# chandelier.net
KiCad netlist of a schematic drawn in EAGLE
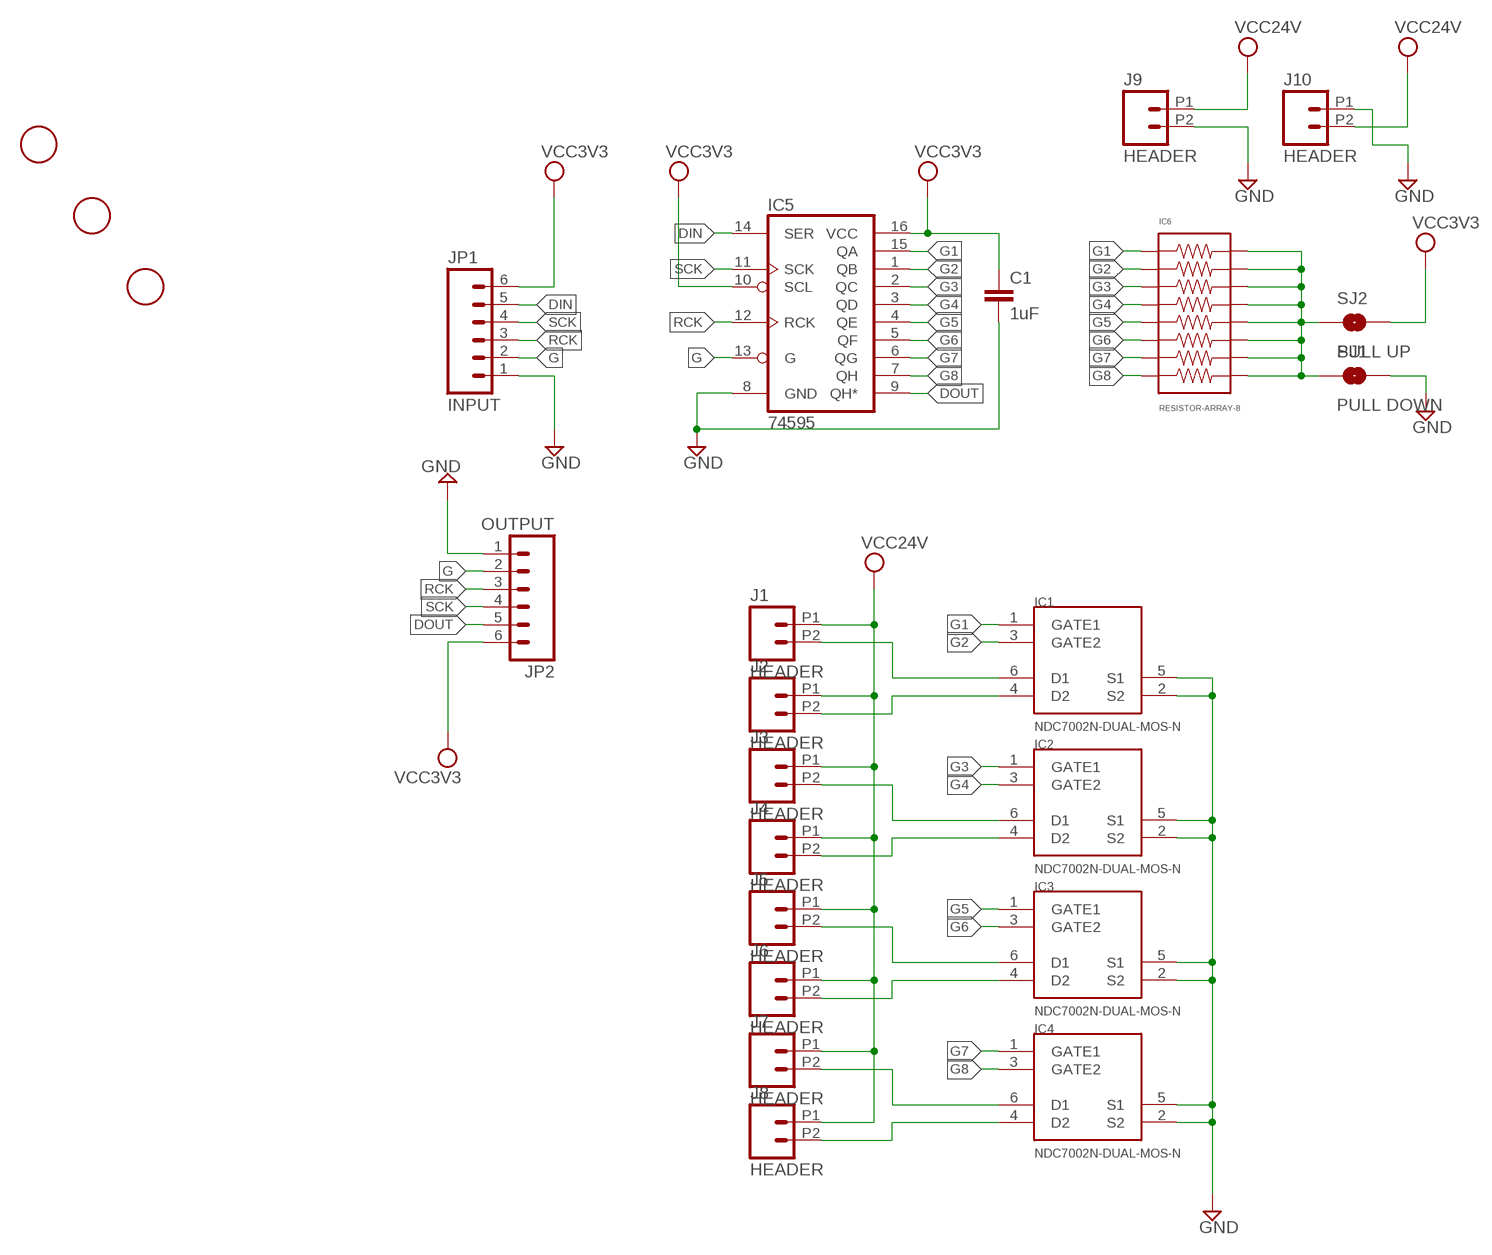
[diagram p0: schematic, sheet 1]

(export (version "E")
  (design (tool "Eeschema 10.0.6"))
  (components
    (comp (ref "C1")
      (value "1uF")
      (footprint "eagle-import:0805")
      (fields (field (name "PARTNO") "CL21B105KOFNNNE"))
      (libsource (lib "eagle-import") (part "CAP0805"))
    )
    (comp (ref "IC1")
      (value "NDC7002N-DUAL-MOS-N")
      (footprint "eagle-import:SSOT6")
      (fields (field (name "PARTNO") "NDC7002N"))
      (libsource (lib "eagle-import") (part "NDC7002N-DUAL-MOS-N"))
    )
    (comp (ref "IC2")
      (value "NDC7002N-DUAL-MOS-N")
      (footprint "eagle-import:SSOT6")
      (fields (field (name "PARTNO") "NDC7002N"))
      (libsource (lib "eagle-import") (part "NDC7002N-DUAL-MOS-N"))
    )
    (comp (ref "IC3")
      (value "NDC7002N-DUAL-MOS-N")
      (footprint "eagle-import:SSOT6")
      (fields (field (name "PARTNO") "NDC7002N"))
      (libsource (lib "eagle-import") (part "NDC7002N-DUAL-MOS-N"))
    )
    (comp (ref "IC4")
      (value "NDC7002N-DUAL-MOS-N")
      (footprint "eagle-import:SSOT6")
      (fields (field (name "PARTNO") "NDC7002N"))
      (libsource (lib "eagle-import") (part "NDC7002N-DUAL-MOS-N"))
    )
    (comp (ref "IC5")
      (value "74595")
      (footprint "eagle-import:TSSOP16")
      (fields (field (name "PARTNO") "74VHC595MTCX"))
      (libsource (lib "eagle-import") (part "74595"))
    )
    (comp (ref "IC6")
      (value "RESISTOR-ARRAY-8")
      (footprint "eagle-import:CAY16-103J8")
      (fields (field (name "PARTNO") "CAY16-103J8LF"))
      (libsource (lib "eagle-import") (part "RESISTOR-ARRAY-8"))
    )
    (comp (ref "J1")
      (value "HEADER")
      (footprint "eagle-import:1X02-5.08-SCREWTERM")
      (libsource (lib "eagle-import") (part "HEADER"))
    )
    (comp (ref "J2")
      (value "HEADER")
      (footprint "eagle-import:1X02-5.08-SCREWTERM")
      (libsource (lib "eagle-import") (part "HEADER"))
    )
    (comp (ref "J3")
      (value "HEADER")
      (footprint "eagle-import:1X02-5.08-SCREWTERM")
      (libsource (lib "eagle-import") (part "HEADER"))
    )
    (comp (ref "J4")
      (value "HEADER")
      (footprint "eagle-import:1X02-5.08-SCREWTERM")
      (libsource (lib "eagle-import") (part "HEADER"))
    )
    (comp (ref "J5")
      (value "HEADER")
      (footprint "eagle-import:1X02-5.08-SCREWTERM")
      (libsource (lib "eagle-import") (part "HEADER"))
    )
    (comp (ref "J6")
      (value "HEADER")
      (footprint "eagle-import:1X02-5.08-SCREWTERM")
      (libsource (lib "eagle-import") (part "HEADER"))
    )
    (comp (ref "J7")
      (value "HEADER")
      (footprint "eagle-import:1X02-5.08-SCREWTERM")
      (libsource (lib "eagle-import") (part "HEADER"))
    )
    (comp (ref "J8")
      (value "HEADER")
      (footprint "eagle-import:1X02-5.08-SCREWTERM")
      (libsource (lib "eagle-import") (part "HEADER"))
    )
    (comp (ref "J9")
      (value "HEADER")
      (footprint "eagle-import:1X02-5.08-SCREWTERM")
      (libsource (lib "eagle-import") (part "HEADER"))
    )
    (comp (ref "J10")
      (value "HEADER")
      (footprint "eagle-import:1X02-5.08-SCREWTERM")
      (libsource (lib "eagle-import") (part "HEADER"))
    )
    (comp (ref "JP1")
      (value "INPUT")
      (footprint "eagle-import:1X06-SIP_LOCK")
      (libsource (lib "eagle-import") (part "M06SIP_LOCK"))
    )
    (comp (ref "JP2")
      (value "OUTPUT")
      (footprint "eagle-import:1X06-SIP_LOCK")
      (libsource (lib "eagle-import") (part "M06SIP_LOCK"))
    )
    (comp (ref "SJ1")
      (value "PULL DOWN")
      (footprint "eagle-import:SJ_2S-TRACE")
      (libsource (lib "eagle-import") (part "SOLDERJUMPERTRACE"))
    )
    (comp (ref "SJ2")
      (value "PULL UP")
      (footprint "eagle-import:SJ_2S-NO")
      (libsource (lib "eagle-import") (part "SOLDERJUMPERNO"))
    )
    (comp (ref "U$1")
      (value "FIDUCIAL")
      (footprint "eagle-import:FIDUCIAL_1MM")
      (libsource (lib "eagle-import") (part "FIDUCIAL"))
    )
    (comp (ref "U$4")
      (value "FIDUCIAL")
      (footprint "eagle-import:FIDUCIAL_1MM")
      (libsource (lib "eagle-import") (part "FIDUCIAL"))
    )
    (comp (ref "U$5")
      (value "FIDUCIAL")
      (footprint "eagle-import:FIDUCIAL_1MM")
      (libsource (lib "eagle-import") (part "FIDUCIAL"))
    )
  )
  (nets
    (net (code "1") (name "DIN") (class "Default")
      (node (ref "IC5") (pin "14") (pinfunction "SER_14") (pintype "input"))
      (node (ref "JP1") (pin "5") (pinfunction "5_5") (pintype "passive"))
    )
    (net (code "2") (name "DOUT") (class "Default")
      (node (ref "IC5") (pin "9") (pinfunction "QH*_9") (pintype "tri_state"))
      (node (ref "JP2") (pin "5") (pinfunction "5_5") (pintype "passive"))
    )
    (net (code "3") (name "G") (class "Default")
      (node (ref "IC5") (pin "13") (pinfunction "G_13") (pintype "input"))
      (node (ref "JP1") (pin "2") (pinfunction "2_2") (pintype "passive"))
      (node (ref "JP2") (pin "2") (pinfunction "2_2") (pintype "passive"))
    )
    (net (code "4") (name "G1") (class "Default")
      (node (ref "IC1") (pin "1") (pinfunction "GATE1_1") (pintype "bidirectional"))
      (node (ref "IC5") (pin "15") (pinfunction "QA_15") (pintype "tri_state"))
      (node (ref "IC6") (pin "2") (pinfunction "2_2") (pintype "passive"))
    )
    (net (code "5") (name "G2") (class "Default")
      (node (ref "IC1") (pin "3") (pinfunction "GATE2_3") (pintype "bidirectional"))
      (node (ref "IC5") (pin "1") (pinfunction "QB_1") (pintype "tri_state"))
      (node (ref "IC6") (pin "4") (pinfunction "4_4") (pintype "passive"))
    )
    (net (code "6") (name "G3") (class "Default")
      (node (ref "IC2") (pin "1") (pinfunction "GATE1_1") (pintype "bidirectional"))
      (node (ref "IC5") (pin "2") (pinfunction "QC_2") (pintype "tri_state"))
      (node (ref "IC6") (pin "6") (pinfunction "6_6") (pintype "passive"))
    )
    (net (code "7") (name "G4") (class "Default")
      (node (ref "IC2") (pin "3") (pinfunction "GATE2_3") (pintype "bidirectional"))
      (node (ref "IC5") (pin "3") (pinfunction "QD_3") (pintype "tri_state"))
      (node (ref "IC6") (pin "8") (pinfunction "8_8") (pintype "passive"))
    )
    (net (code "8") (name "G5") (class "Default")
      (node (ref "IC3") (pin "1") (pinfunction "GATE1_1") (pintype "bidirectional"))
      (node (ref "IC5") (pin "4") (pinfunction "QE_4") (pintype "tri_state"))
      (node (ref "IC6") (pin "10") (pinfunction "10_10") (pintype "passive"))
    )
    (net (code "9") (name "G6") (class "Default")
      (node (ref "IC3") (pin "3") (pinfunction "GATE2_3") (pintype "bidirectional"))
      (node (ref "IC5") (pin "5") (pinfunction "QF_5") (pintype "tri_state"))
      (node (ref "IC6") (pin "12") (pinfunction "12_12") (pintype "passive"))
    )
    (net (code "10") (name "G7") (class "Default")
      (node (ref "IC4") (pin "1") (pinfunction "GATE1_1") (pintype "bidirectional"))
      (node (ref "IC5") (pin "6") (pinfunction "QG_6") (pintype "tri_state"))
      (node (ref "IC6") (pin "14") (pinfunction "14_14") (pintype "passive"))
    )
    (net (code "11") (name "G8") (class "Default")
      (node (ref "IC4") (pin "3") (pinfunction "GATE2_3") (pintype "bidirectional"))
      (node (ref "IC5") (pin "7") (pinfunction "QH_7") (pintype "tri_state"))
      (node (ref "IC6") (pin "16") (pinfunction "16_16") (pintype "passive"))
    )
    (net (code "12") (name "GND") (class "Default")
      (node (ref "C1") (pin "2") (pinfunction "2_2") (pintype "passive"))
      (node (ref "IC1") (pin "2") (pinfunction "S2_2") (pintype "bidirectional"))
      (node (ref "IC1") (pin "5") (pinfunction "S1_5") (pintype "bidirectional"))
      (node (ref "IC2") (pin "2") (pinfunction "S2_2") (pintype "bidirectional"))
      (node (ref "IC2") (pin "5") (pinfunction "S1_5") (pintype "bidirectional"))
      (node (ref "IC3") (pin "2") (pinfunction "S2_2") (pintype "bidirectional"))
      (node (ref "IC3") (pin "5") (pinfunction "S1_5") (pintype "bidirectional"))
      (node (ref "IC4") (pin "2") (pinfunction "S2_2") (pintype "bidirectional"))
      (node (ref "IC4") (pin "5") (pinfunction "S1_5") (pintype "bidirectional"))
      (node (ref "IC5") (pin "8") (pinfunction "GND_8") (pintype "power_in"))
      (node (ref "J10") (pin "P1") (pinfunction "2_P1") (pintype "passive"))
      (node (ref "J9") (pin "P2") (pinfunction "1_P2") (pintype "passive"))
      (node (ref "JP1") (pin "1") (pinfunction "1_1") (pintype "passive"))
      (node (ref "JP2") (pin "1") (pinfunction "1_1") (pintype "passive"))
      (node (ref "SJ1") (pin "2") (pinfunction "2_2") (pintype "passive"))
    )
    (net (code "13") (name "Net-(IC1-D1)") (class "Default")
      (node (ref "IC1") (pin "6") (pinfunction "D1_6") (pintype "bidirectional"))
      (node (ref "J1") (pin "P2") (pinfunction "1_P2") (pintype "passive"))
    )
    (net (code "14") (name "Net-(IC1-D2)") (class "Default")
      (node (ref "IC1") (pin "4") (pinfunction "D2_4") (pintype "bidirectional"))
      (node (ref "J2") (pin "P2") (pinfunction "1_P2") (pintype "passive"))
    )
    (net (code "15") (name "Net-(IC2-D1)") (class "Default")
      (node (ref "IC2") (pin "6") (pinfunction "D1_6") (pintype "bidirectional"))
      (node (ref "J3") (pin "P2") (pinfunction "1_P2") (pintype "passive"))
    )
    (net (code "16") (name "Net-(IC2-D2)") (class "Default")
      (node (ref "IC2") (pin "4") (pinfunction "D2_4") (pintype "bidirectional"))
      (node (ref "J4") (pin "P2") (pinfunction "1_P2") (pintype "passive"))
    )
    (net (code "17") (name "Net-(IC3-D1)") (class "Default")
      (node (ref "IC3") (pin "6") (pinfunction "D1_6") (pintype "bidirectional"))
      (node (ref "J5") (pin "P2") (pinfunction "1_P2") (pintype "passive"))
    )
    (net (code "18") (name "Net-(IC3-D2)") (class "Default")
      (node (ref "IC3") (pin "4") (pinfunction "D2_4") (pintype "bidirectional"))
      (node (ref "J6") (pin "P2") (pinfunction "1_P2") (pintype "passive"))
    )
    (net (code "19") (name "Net-(IC4-D1)") (class "Default")
      (node (ref "IC4") (pin "6") (pinfunction "D1_6") (pintype "bidirectional"))
      (node (ref "J7") (pin "P2") (pinfunction "1_P2") (pintype "passive"))
    )
    (net (code "20") (name "Net-(IC4-D2)") (class "Default")
      (node (ref "IC4") (pin "4") (pinfunction "D2_4") (pintype "bidirectional"))
      (node (ref "J8") (pin "P2") (pinfunction "1_P2") (pintype "passive"))
    )
    (net (code "21") (name "Net-(IC6-Pad1)") (class "Default")
      (node (ref "IC6") (pin "1") (pinfunction "1_1") (pintype "passive"))
      (node (ref "IC6") (pin "11") (pinfunction "11_11") (pintype "passive"))
      (node (ref "IC6") (pin "13") (pinfunction "13_13") (pintype "passive"))
      (node (ref "IC6") (pin "15") (pinfunction "15_15") (pintype "passive"))
      (node (ref "IC6") (pin "3") (pinfunction "3_3") (pintype "passive"))
      (node (ref "IC6") (pin "5") (pinfunction "5_5") (pintype "passive"))
      (node (ref "IC6") (pin "7") (pinfunction "7_7") (pintype "passive"))
      (node (ref "IC6") (pin "9") (pinfunction "9_9") (pintype "passive"))
      (node (ref "SJ1") (pin "1") (pinfunction "1_1") (pintype "passive"))
      (node (ref "SJ2") (pin "1") (pinfunction "1_1") (pintype "passive"))
    )
    (net (code "22") (name "RCK") (class "Default")
      (node (ref "IC5") (pin "12") (pinfunction "RCK_12") (pintype "input"))
      (node (ref "JP1") (pin "3") (pinfunction "3_3") (pintype "passive"))
      (node (ref "JP2") (pin "3") (pinfunction "3_3") (pintype "passive"))
    )
    (net (code "23") (name "SCK") (class "Default")
      (node (ref "IC5") (pin "11") (pinfunction "SCK_11") (pintype "input"))
      (node (ref "JP1") (pin "4") (pinfunction "4_4") (pintype "passive"))
      (node (ref "JP2") (pin "4") (pinfunction "4_4") (pintype "passive"))
    )
    (net (code "24") (name "VCC3V3") (class "Default")
      (node (ref "C1") (pin "1") (pinfunction "1_1") (pintype "passive"))
      (node (ref "IC5") (pin "10") (pinfunction "SCL_10") (pintype "input"))
      (node (ref "IC5") (pin "16") (pinfunction "VCC_16") (pintype "power_in"))
      (node (ref "JP1") (pin "6") (pinfunction "6_6") (pintype "passive"))
      (node (ref "JP2") (pin "6") (pinfunction "6_6") (pintype "passive"))
      (node (ref "SJ2") (pin "2") (pinfunction "2_2") (pintype "passive"))
    )
    (net (code "25") (name "VCC24V") (class "Default")
      (node (ref "J1") (pin "P1") (pinfunction "2_P1") (pintype "passive"))
      (node (ref "J10") (pin "P2") (pinfunction "1_P2") (pintype "passive"))
      (node (ref "J2") (pin "P1") (pinfunction "2_P1") (pintype "passive"))
      (node (ref "J3") (pin "P1") (pinfunction "2_P1") (pintype "passive"))
      (node (ref "J4") (pin "P1") (pinfunction "2_P1") (pintype "passive"))
      (node (ref "J5") (pin "P1") (pinfunction "2_P1") (pintype "passive"))
      (node (ref "J6") (pin "P1") (pinfunction "2_P1") (pintype "passive"))
      (node (ref "J7") (pin "P1") (pinfunction "2_P1") (pintype "passive"))
      (node (ref "J8") (pin "P1") (pinfunction "2_P1") (pintype "passive"))
      (node (ref "J9") (pin "P1") (pinfunction "2_P1") (pintype "passive"))
    )
  )
)
